# ESP32.net
KiCad netlist of a schematic drawn in Altium Designer
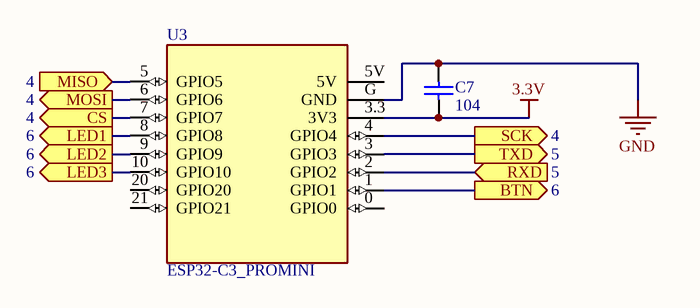
[diagram p0: ESP32.SchDoc]

(export (version "E")
  (design (tool "Eeschema 10.0.6"))
  (components
    (comp (ref "C7")
      (value "104")
      (footprint "tu gom")
      (description "Cắm")
      (libsource (lib "Altium_Lib_by_KhueNguyenCreator") (part "Tu gom 104 50V"))
    )
    (comp (ref "U3")
      (value "ESP32-C3_PROMINI")
      (footprint "MODULE_ESP32-C3_SUPERMINI_TH")
      (description "Super tiny ESP32-C3 board")
      (fields (field (name "MF") "Espressif Systems") (field (name "MP") "ESP32-C3 SuperMini_TH"))
      (libsource (lib "ESP32-C3_SUPERMINI_TH") (part "ESP32-C3_SUPERMINI_TH"))
    )
  )
  (nets
    (net (code "1") (name "/BTN") (class "Default")
      (node (ref "U3") (pin "1") (pinfunction "GPIO1_1") (pintype "bidirectional"))
    )
    (net (code "2") (name "/CS") (class "Default")
      (node (ref "U3") (pin "7") (pinfunction "GPIO7_7") (pintype "bidirectional"))
    )
    (net (code "3") (name "/LED1") (class "Default")
      (node (ref "U3") (pin "8") (pinfunction "GPIO8_8") (pintype "bidirectional"))
    )
    (net (code "4") (name "/LED2") (class "Default")
      (node (ref "U3") (pin "9") (pinfunction "GPIO9_9") (pintype "bidirectional"))
    )
    (net (code "5") (name "/LED3") (class "Default")
      (node (ref "U3") (pin "10") (pinfunction "GPIO10_10") (pintype "bidirectional"))
    )
    (net (code "6") (name "/MISO") (class "Default")
      (node (ref "U3") (pin "5") (pinfunction "GPIO5_5") (pintype "bidirectional"))
    )
    (net (code "7") (name "/MOSI") (class "Default")
      (node (ref "U3") (pin "6") (pinfunction "GPIO6_6") (pintype "bidirectional"))
    )
    (net (code "8") (name "/RXD") (class "Default")
      (node (ref "U3") (pin "2") (pinfunction "GPIO2_2") (pintype "bidirectional"))
    )
    (net (code "9") (name "/SCK") (class "Default")
      (node (ref "U3") (pin "4") (pinfunction "GPIO4_4") (pintype "bidirectional"))
    )
    (net (code "10") (name "/TXD") (class "Default")
      (node (ref "U3") (pin "3") (pinfunction "GPIO3_3") (pintype "bidirectional"))
    )
    (net (code "11") (name "3.3V") (class "Default")
      (node (ref "C7") (pin "1") (pinfunction "1_1") (pintype "passive"))
      (node (ref "U3") (pin "3.3") (pinfunction "3V3_3.3") (pintype "power_in"))
    )
    (net (code "12") (name "GND") (class "Default")
      (node (ref "C7") (pin "2") (pinfunction "2_2") (pintype "passive"))
      (node (ref "U3") (pin "G") (pinfunction "GND_G") (pintype "power_in"))
    )
    (net (code "13") (name "unconnected-(U3-GPIO0-Pad0)") (class "Default")
      (node (ref "U3") (pin "0") (pinfunction "GPIO0_0") (pintype "bidirectional"))
    )
    (net (code "14") (name "unconnected-(U3-GPIO20-Pad20)") (class "Default")
      (node (ref "U3") (pin "20") (pinfunction "GPIO20_20") (pintype "bidirectional"))
    )
    (net (code "15") (name "unconnected-(U3-GPIO21-Pad21)") (class "Default")
      (node (ref "U3") (pin "21") (pinfunction "GPIO21_21") (pintype "bidirectional"))
    )
    (net (code "16") (name "unconnected-(U3-Pad5V)") (class "Default")
      (node (ref "U3") (pin "5V") (pinfunction "5V_5V") (pintype "power_in"))
    )
  )
)
